# AMP_LM386M-1.net
KiCad netlist of a schematic drawn in Altium Designer
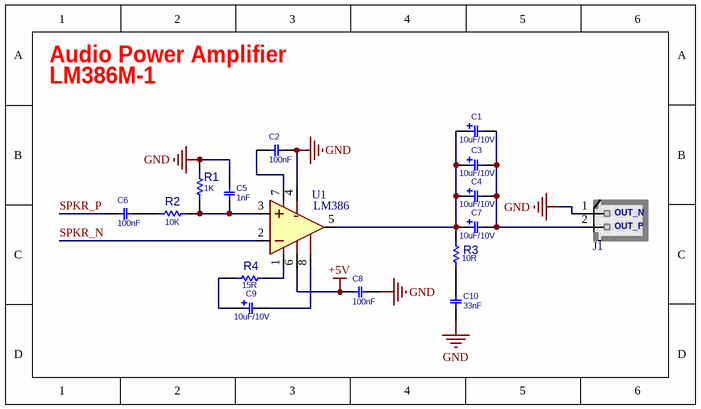
[diagram p0: AMP LM386M-1.SchDoc]

(export (version "E")
  (design (tool "Eeschema 10.0.6"))
  (components
    (comp (ref "C1")
      (value "10uF/10V")
      (footprint "C_TN_A")
      (description "CAP, SMD, TAN")
      (libsource (lib "PW Components 97_492") (part "CAP_SMD_TAN"))
    )
    (comp (ref "C2")
      (value "100nF")
      (footprint "C0603")
      (description "CAP, SMD, MLCC")
      (fields (field (name "MANF_P#") "MANF_PART#") (field (name "MANF") "Murata"))
      (libsource (lib "PW Components 97_492") (part "CAP_SMD_MLCC"))
    )
    (comp (ref "C3")
      (value "10uF/10V")
      (footprint "C_TN_A")
      (description "CAP, SMD, TAN")
      (libsource (lib "PW Components 97_492") (part "CAP_SMD_TAN"))
    )
    (comp (ref "C4")
      (value "10uF/10V")
      (footprint "C_TN_A")
      (description "CAP, SMD, TAN")
      (libsource (lib "PW Components 97_492") (part "CAP_SMD_TAN"))
    )
    (comp (ref "C5")
      (value "1nF")
      (footprint "C0603")
      (description "CAP, SMD, MLCC")
      (fields (field (name "MANF_P#") "MANF_PART#") (field (name "MANF") "Murata"))
      (libsource (lib "PW Components 97_492") (part "CAP_SMD_MLCC"))
    )
    (comp (ref "C6")
      (value "100nF")
      (footprint "C0603")
      (description "CAP, SMD, MLCC")
      (fields (field (name "MANF_P#") "MANF_PART#") (field (name "MANF") "Murata"))
      (libsource (lib "PW Components 97_492") (part "CAP_SMD_MLCC"))
    )
    (comp (ref "C7")
      (value "10uF/10V")
      (footprint "C_TN_A")
      (description "CAP, SMD, TAN")
      (libsource (lib "PW Components 97_492") (part "CAP_SMD_TAN"))
    )
    (comp (ref "C8")
      (value "100nF")
      (footprint "C0603")
      (description "CAP, SMD, MLCC")
      (fields (field (name "MANF_P#") "MANF_PART#") (field (name "MANF") "Murata"))
      (libsource (lib "PW Components 97_492") (part "CAP_SMD_MLCC"))
    )
    (comp (ref "C9")
      (value "10uF/10V")
      (footprint "C_TN_A")
      (description "CAP, SMD, TAN")
      (libsource (lib "PW Components 97_492") (part "CAP_SMD_TAN"))
    )
    (comp (ref "C10")
      (value "33nF")
      (footprint "C0603")
      (description "CAP, SMD, MLCC")
      (fields (field (name "MANF_P#") "MANF_PART#") (field (name "MANF") "Murata"))
      (libsource (lib "PW Components 97_492") (part "CAP_SMD_MLCC"))
    )
    (comp (ref "J1")
      (value "HHDR_2")
      (footprint "XH_2")
      (description "CONN, 5264-2A, 2.54mm, 2Pos")
      (libsource (lib "PW Components 97_492") (part "CONN_PW_SPKR_5264_2A_254MM_1X2"))
    )
    (comp (ref "R1")
      (value "1K")
      (footprint "R0603")
      (description "RES, SMD")
      (fields (field (name "MANF_P#") "RK73H1ETTP4701F") (field (name "MANF") "KOA SPEER"))
      (libsource (lib "PW Components 97_492") (part "RES_SMD"))
    )
    (comp (ref "R2")
      (value "10K")
      (footprint "R0603")
      (description "RES, SMD")
      (fields (field (name "MANF_P#") "RK73H1ETTP4701F") (field (name "MANF") "KOA SPEER"))
      (libsource (lib "PW Components 97_492") (part "RES_SMD"))
    )
    (comp (ref "R3")
      (value "10R")
      (footprint "R0603")
      (description "RES, SMD")
      (fields (field (name "MANF_P#") "RK73H1ETTP4701F") (field (name "MANF") "KOA SPEER"))
      (libsource (lib "PW Components 97_492") (part "RES_SMD"))
    )
    (comp (ref "R4")
      (value "15R")
      (footprint "R0603")
      (description "RES, SMD")
      (fields (field (name "MANF_P#") "RK73H1ETTP4701F") (field (name "MANF") "KOA SPEER"))
      (libsource (lib "PW Components 97_492") (part "RES_SMD"))
    )
    (comp (ref "U1")
      (value "LM386")
      (footprint "SO_8")
      (description "AMP, Audio, Low Voltage, Power Amp")
      (fields (field (name "MANF") "Texas Instruments") (field (name "MANF_P#") "LM386MX-1"))
      (libsource (lib "PW Components 97_492") (part "LM386_SOP8"))
    )
  )
  (nets
    (net (code "1") (name "+5V") (class "Default")
      (node (ref "C8") (pin "1") (pinfunction "1_1") (pintype "passive"))
      (node (ref "U1") (pin "6") (pinfunction "VS_6") (pintype "passive"))
    )
    (net (code "2") (name "/SPKR_N") (class "Default")
      (node (ref "U1") (pin "2") (pinfunction "IN-_2") (pintype "passive"))
    )
    (net (code "3") (name "/SPKR_P") (class "Default")
      (node (ref "C6") (pin "2") (pinfunction "2_2") (pintype "passive"))
    )
    (net (code "4") (name "GND") (class "Default")
      (node (ref "C10") (pin "1") (pinfunction "1_1") (pintype "passive"))
      (node (ref "C2") (pin "1") (pinfunction "1_1") (pintype "passive"))
      (node (ref "C5") (pin "1") (pinfunction "1_1") (pintype "passive"))
      (node (ref "C8") (pin "2") (pinfunction "2_2") (pintype "passive"))
      (node (ref "J1") (pin "1") (pinfunction "1_1") (pintype "passive"))
      (node (ref "R1") (pin "2") (pinfunction "2_2") (pintype "passive"))
      (node (ref "U1") (pin "4") (pinfunction "GND_4") (pintype "passive"))
    )
    (net (code "5") (name "Net-(C1-Pad2)") (class "Default")
      (node (ref "C1") (pin "2") (pinfunction "2_2") (pintype "passive"))
      (node (ref "C3") (pin "2") (pinfunction "2_2") (pintype "passive"))
      (node (ref "C4") (pin "2") (pinfunction "2_2") (pintype "passive"))
      (node (ref "C7") (pin "2") (pinfunction "2_2") (pintype "passive"))
      (node (ref "J1") (pin "2") (pinfunction "2_2") (pintype "passive"))
    )
    (net (code "6") (name "Net-(C6-Pad1)") (class "Default")
      (node (ref "C6") (pin "1") (pinfunction "1_1") (pintype "passive"))
      (node (ref "R2") (pin "1") (pinfunction "1_1") (pintype "passive"))
    )
    (net (code "7") (name "Net-(C9-Pad1)") (class "Default")
      (node (ref "C9") (pin "1") (pinfunction "1_1") (pintype "passive"))
      (node (ref "R4") (pin "2") (pinfunction "2_2") (pintype "passive"))
    )
    (net (code "8") (name "Net-(C9-Pad2)") (class "Default")
      (node (ref "C9") (pin "2") (pinfunction "2_2") (pintype "passive"))
      (node (ref "U1") (pin "8") (pinfunction "GAIN_8") (pintype "passive"))
    )
    (net (code "9") (name "Net-(C10-Pad2)") (class "Default")
      (node (ref "C10") (pin "2") (pinfunction "2_2") (pintype "passive"))
      (node (ref "R3") (pin "1") (pinfunction "1_1") (pintype "passive"))
    )
    (net (code "10") (name "Net-(R4-Pad1)") (class "Default")
      (node (ref "R4") (pin "1") (pinfunction "1_1") (pintype "passive"))
      (node (ref "U1") (pin "1") (pinfunction "GAIN_1") (pintype "passive"))
    )
    (net (code "11") (name "Net-(U1-BYPASS)") (class "Default")
      (node (ref "C2") (pin "2") (pinfunction "2_2") (pintype "passive"))
      (node (ref "U1") (pin "7") (pinfunction "BYPASS_7") (pintype "passive"))
    )
    (net (code "12") (name "Net-(U1-IN+)") (class "Default")
      (node (ref "C5") (pin "2") (pinfunction "2_2") (pintype "passive"))
      (node (ref "R1") (pin "1") (pinfunction "1_1") (pintype "passive"))
      (node (ref "R2") (pin "2") (pinfunction "2_2") (pintype "passive"))
      (node (ref "U1") (pin "3") (pinfunction "IN+_3") (pintype "passive"))
    )
    (net (code "13") (name "Net-(U1-VOUT)") (class "Default")
      (node (ref "C1") (pin "1") (pinfunction "1_1") (pintype "passive"))
      (node (ref "C3") (pin "1") (pinfunction "1_1") (pintype "passive"))
      (node (ref "C4") (pin "1") (pinfunction "1_1") (pintype "passive"))
      (node (ref "C7") (pin "1") (pinfunction "1_1") (pintype "passive"))
      (node (ref "R3") (pin "2") (pinfunction "2_2") (pintype "passive"))
      (node (ref "U1") (pin "5") (pinfunction "VOUT_5") (pintype "passive"))
    )
  )
)
